# DualExpVCA.net
KiCad netlist of a schematic drawn in EAGLE
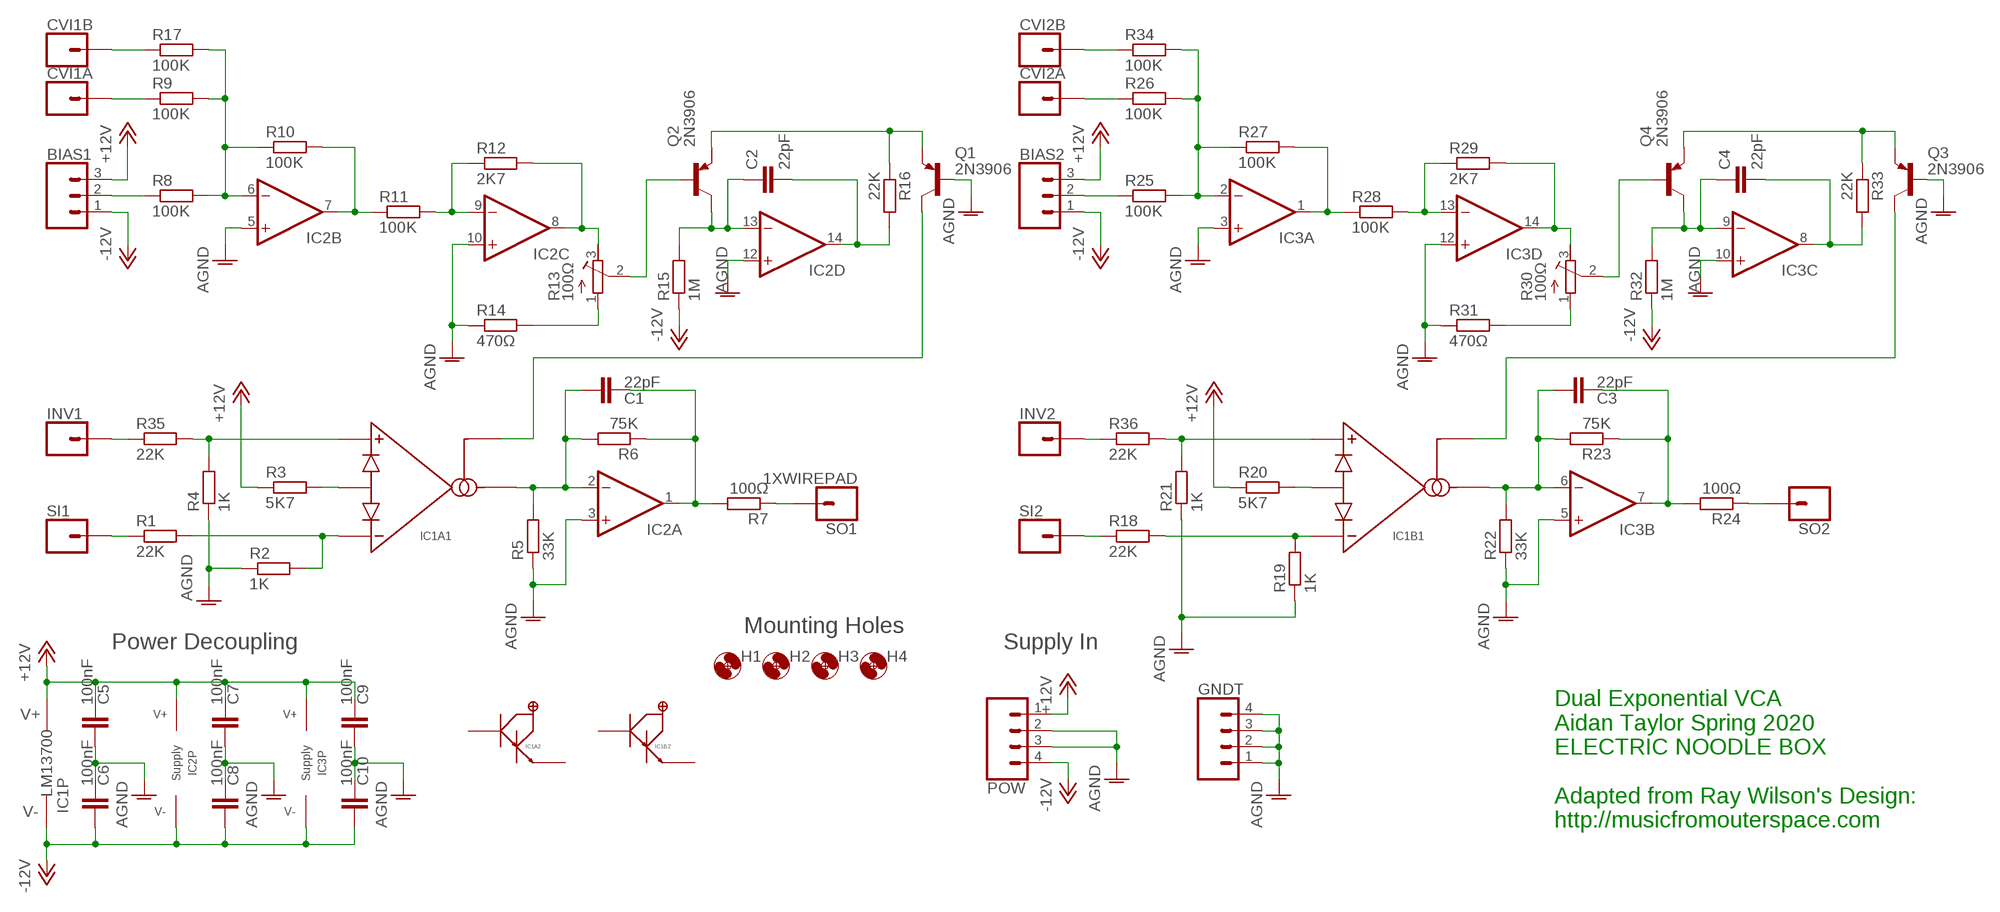
[diagram p0: schematic, sheet 1]

(export (version "E")
  (design (tool "Eeschema 10.0.6"))
  (components
    (comp (ref "BIAS1")
      (value "3XWIREPAD")
      (footprint "eagle-import:1X03")
      (libsource (lib "eagle-import") (part "3XWIREPAD"))
    )
    (comp (ref "BIAS2")
      (value "3XWIREPAD")
      (footprint "eagle-import:1X03")
      (libsource (lib "eagle-import") (part "3XWIREPAD"))
    )
    (comp (ref "C1")
      (value "22pF")
      (footprint "eagle-import:C050-025X075")
      (libsource (lib "eagle-import") (part "C-EU050-025X075"))
    )
    (comp (ref "C2")
      (value "22pF")
      (footprint "eagle-import:C050-025X075")
      (libsource (lib "eagle-import") (part "C-EU050-025X075"))
    )
    (comp (ref "C3")
      (value "22pF")
      (footprint "eagle-import:C050-025X075")
      (libsource (lib "eagle-import") (part "C-EU050-025X075"))
    )
    (comp (ref "C4")
      (value "22pF")
      (footprint "eagle-import:C050-025X075")
      (libsource (lib "eagle-import") (part "C-EU050-025X075"))
    )
    (comp (ref "C5")
      (value "100nF")
      (footprint "eagle-import:C050-025X075")
      (libsource (lib "eagle-import") (part "C-EU050-025X075"))
    )
    (comp (ref "C6")
      (value "100nF")
      (footprint "eagle-import:C050-025X075")
      (libsource (lib "eagle-import") (part "C-EU050-025X075"))
    )
    (comp (ref "C7")
      (value "100nF")
      (footprint "eagle-import:C050-025X075")
      (libsource (lib "eagle-import") (part "C-EU050-025X075"))
    )
    (comp (ref "C8")
      (value "100nF")
      (footprint "eagle-import:C050-025X075")
      (libsource (lib "eagle-import") (part "C-EU050-025X075"))
    )
    (comp (ref "C9")
      (value "100nF")
      (footprint "eagle-import:C050-025X075")
      (libsource (lib "eagle-import") (part "C-EU050-025X075"))
    )
    (comp (ref "C10")
      (value "100nF")
      (footprint "eagle-import:C050-025X075")
      (libsource (lib "eagle-import") (part "C-EU050-025X075"))
    )
    (comp (ref "CVI1A")
      (value "1XWIREPAD")
      (footprint "eagle-import:1X01")
      (libsource (lib "eagle-import") (part "1XWIREPAD"))
    )
    (comp (ref "CVI1B")
      (value "1XWIREPAD")
      (footprint "eagle-import:1X01")
      (libsource (lib "eagle-import") (part "1XWIREPAD"))
    )
    (comp (ref "CVI2A")
      (value "1XWIREPAD")
      (footprint "eagle-import:1X01")
      (libsource (lib "eagle-import") (part "1XWIREPAD"))
    )
    (comp (ref "CVI2B")
      (value "1XWIREPAD")
      (footprint "eagle-import:1X01")
      (libsource (lib "eagle-import") (part "1XWIREPAD"))
    )
    (comp (ref "GNDT")
      (value "4XWIREPAD")
      (footprint "eagle-import:1X04")
      (libsource (lib "eagle-import") (part "4XWIREPAD"))
    )
    (comp (ref "H1")
      (value "MOUNT-HOLE3.2")
      (footprint "eagle-import:3,2")
      (libsource (lib "eagle-import") (part "MOUNT-HOLE3.2"))
    )
    (comp (ref "H2")
      (value "MOUNT-HOLE3.2")
      (footprint "eagle-import:3,2")
      (libsource (lib "eagle-import") (part "MOUNT-HOLE3.2"))
    )
    (comp (ref "H3")
      (value "MOUNT-HOLE3.2")
      (footprint "eagle-import:3,2")
      (libsource (lib "eagle-import") (part "MOUNT-HOLE3.2"))
    )
    (comp (ref "H4")
      (value "MOUNT-HOLE3.2")
      (footprint "eagle-import:3,2")
      (libsource (lib "eagle-import") (part "MOUNT-HOLE3.2"))
    )
    (comp (ref "IC1")
      (value "LM13700_DIP")
      (footprint "eagle-import:DIL16")
      (libsource (lib "eagle-import") (part "LM13700_DIP"))
    )
    (comp (ref "IC2")
      (value "TL0X4_DIP")
      (footprint "eagle-import:DIL14")
      (libsource (lib "eagle-import") (part "TL0X4_DIP"))
    )
    (comp (ref "IC3")
      (value "TL0X4_DIP")
      (footprint "eagle-import:DIL14")
      (libsource (lib "eagle-import") (part "TL0X4_DIP"))
    )
    (comp (ref "INV1")
      (value "1XWIREPAD")
      (footprint "eagle-import:1X01")
      (libsource (lib "eagle-import") (part "1XWIREPAD"))
    )
    (comp (ref "INV2")
      (value "1XWIREPAD")
      (footprint "eagle-import:1X01")
      (libsource (lib "eagle-import") (part "1XWIREPAD"))
    )
    (comp (ref "POW")
      (value "4XMOLEX")
      (footprint "eagle-import:MOLEX-1X4")
      (libsource (lib "eagle-import") (part "4XMOLEX"))
    )
    (comp (ref "Q1")
      (value "2N3906")
      (footprint "eagle-import:TO92")
      (libsource (lib "eagle-import") (part "2N3906"))
    )
    (comp (ref "Q2")
      (value "2N3906")
      (footprint "eagle-import:TO92")
      (libsource (lib "eagle-import") (part "2N3906"))
    )
    (comp (ref "Q3")
      (value "2N3906")
      (footprint "eagle-import:TO92")
      (libsource (lib "eagle-import") (part "2N3906"))
    )
    (comp (ref "Q4")
      (value "2N3906")
      (footprint "eagle-import:TO92")
      (libsource (lib "eagle-import") (part "2N3906"))
    )
    (comp (ref "R1")
      (value "22K")
      (footprint "eagle-import:0207_10")
      (libsource (lib "eagle-import") (part "R-EU_0207/10"))
    )
    (comp (ref "R2")
      (value "1K")
      (footprint "eagle-import:0207_10")
      (libsource (lib "eagle-import") (part "R-EU_0207/10"))
    )
    (comp (ref "R3")
      (value "5K7")
      (footprint "eagle-import:0207_10")
      (libsource (lib "eagle-import") (part "R-EU_0207/10"))
    )
    (comp (ref "R4")
      (value "1K")
      (footprint "eagle-import:0207_10")
      (libsource (lib "eagle-import") (part "R-EU_0207/10"))
    )
    (comp (ref "R5")
      (value "33K")
      (footprint "eagle-import:0207_10")
      (libsource (lib "eagle-import") (part "R-EU_0207/10"))
    )
    (comp (ref "R6")
      (value "75K")
      (footprint "eagle-import:0207_10")
      (libsource (lib "eagle-import") (part "R-EU_0207/10"))
    )
    (comp (ref "R7")
      (value "100Ω")
      (footprint "eagle-import:0207_10")
      (libsource (lib "eagle-import") (part "R-EU_0207/10"))
    )
    (comp (ref "R8")
      (value "100K")
      (footprint "eagle-import:0207_10")
      (libsource (lib "eagle-import") (part "R-EU_0207/10"))
    )
    (comp (ref "R9")
      (value "100K")
      (footprint "eagle-import:0207_10")
      (libsource (lib "eagle-import") (part "R-EU_0207/10"))
    )
    (comp (ref "R10")
      (value "100K")
      (footprint "eagle-import:0207_10")
      (libsource (lib "eagle-import") (part "R-EU_0207/10"))
    )
    (comp (ref "R11")
      (value "100K")
      (footprint "eagle-import:0207_10")
      (libsource (lib "eagle-import") (part "R-EU_0207/10"))
    )
    (comp (ref "R12")
      (value "2K7")
      (footprint "eagle-import:0207_10")
      (libsource (lib "eagle-import") (part "R-EU_0207/10"))
    )
    (comp (ref "R13")
      (value "100Ω")
      (footprint "eagle-import:RTRIM3296W")
      (libsource (lib "eagle-import") (part "R-TRIMM3296W"))
    )
    (comp (ref "R14")
      (value "470Ω")
      (footprint "eagle-import:0207_10")
      (libsource (lib "eagle-import") (part "R-EU_0207/10"))
    )
    (comp (ref "R15")
      (value "1M")
      (footprint "eagle-import:0207_10")
      (libsource (lib "eagle-import") (part "R-EU_0207/10"))
    )
    (comp (ref "R16")
      (value "22K")
      (footprint "eagle-import:0207_10")
      (libsource (lib "eagle-import") (part "R-EU_0207/10"))
    )
    (comp (ref "R17")
      (value "100K")
      (footprint "eagle-import:0207_10")
      (libsource (lib "eagle-import") (part "R-EU_0207/10"))
    )
    (comp (ref "R18")
      (value "22K")
      (footprint "eagle-import:0207_10")
      (libsource (lib "eagle-import") (part "R-EU_0207/10"))
    )
    (comp (ref "R19")
      (value "1K")
      (footprint "eagle-import:0207_10")
      (libsource (lib "eagle-import") (part "R-EU_0207/10"))
    )
    (comp (ref "R20")
      (value "5K7")
      (footprint "eagle-import:0207_10")
      (libsource (lib "eagle-import") (part "R-EU_0207/10"))
    )
    (comp (ref "R21")
      (value "1K")
      (footprint "eagle-import:0207_10")
      (libsource (lib "eagle-import") (part "R-EU_0207/10"))
    )
    (comp (ref "R22")
      (value "33K")
      (footprint "eagle-import:0207_10")
      (libsource (lib "eagle-import") (part "R-EU_0207/10"))
    )
    (comp (ref "R23")
      (value "75K")
      (footprint "eagle-import:0207_10")
      (libsource (lib "eagle-import") (part "R-EU_0207/10"))
    )
    (comp (ref "R24")
      (value "100Ω")
      (footprint "eagle-import:0207_10")
      (libsource (lib "eagle-import") (part "R-EU_0207/10"))
    )
    (comp (ref "R25")
      (value "100K")
      (footprint "eagle-import:0207_10")
      (libsource (lib "eagle-import") (part "R-EU_0207/10"))
    )
    (comp (ref "R26")
      (value "100K")
      (footprint "eagle-import:0207_10")
      (libsource (lib "eagle-import") (part "R-EU_0207/10"))
    )
    (comp (ref "R27")
      (value "100K")
      (footprint "eagle-import:0207_10")
      (libsource (lib "eagle-import") (part "R-EU_0207/10"))
    )
    (comp (ref "R28")
      (value "100K")
      (footprint "eagle-import:0207_10")
      (libsource (lib "eagle-import") (part "R-EU_0207/10"))
    )
    (comp (ref "R29")
      (value "2K7")
      (footprint "eagle-import:0207_10")
      (libsource (lib "eagle-import") (part "R-EU_0207/10"))
    )
    (comp (ref "R30")
      (value "100Ω")
      (footprint "eagle-import:RTRIM3296W")
      (libsource (lib "eagle-import") (part "R-TRIMM3296W"))
    )
    (comp (ref "R31")
      (value "470Ω")
      (footprint "eagle-import:0207_10")
      (libsource (lib "eagle-import") (part "R-EU_0207/10"))
    )
    (comp (ref "R32")
      (value "1M")
      (footprint "eagle-import:0207_10")
      (libsource (lib "eagle-import") (part "R-EU_0207/10"))
    )
    (comp (ref "R33")
      (value "22K")
      (footprint "eagle-import:0207_10")
      (libsource (lib "eagle-import") (part "R-EU_0207/10"))
    )
    (comp (ref "R34")
      (value "100K")
      (footprint "eagle-import:0207_10")
      (libsource (lib "eagle-import") (part "R-EU_0207/10"))
    )
    (comp (ref "R35")
      (value "22K")
      (footprint "eagle-import:0207_10")
      (libsource (lib "eagle-import") (part "R-EU_0207/10"))
    )
    (comp (ref "R36")
      (value "22K")
      (footprint "eagle-import:0207_10")
      (libsource (lib "eagle-import") (part "R-EU_0207/10"))
    )
    (comp (ref "SI1")
      (value "1XWIREPAD")
      (footprint "eagle-import:1X01")
      (libsource (lib "eagle-import") (part "1XWIREPAD"))
    )
    (comp (ref "SI2")
      (value "1XWIREPAD")
      (footprint "eagle-import:1X01")
      (libsource (lib "eagle-import") (part "1XWIREPAD"))
    )
    (comp (ref "SO1")
      (value "1XWIREPAD")
      (footprint "eagle-import:1X01")
      (libsource (lib "eagle-import") (part "1XWIREPAD"))
    )
    (comp (ref "SO2")
      (value "1XWIREPAD")
      (footprint "eagle-import:1X01")
      (libsource (lib "eagle-import") (part "1XWIREPAD"))
    )
  )
  (nets
    (net (code "1") (name "+12V") (class "Default")
      (node (ref "BIAS1") (pin "3") (pinfunction "3_3") (pintype "passive"))
      (node (ref "BIAS2") (pin "3") (pinfunction "3_3") (pintype "passive"))
      (node (ref "C5") (pin "2") (pinfunction "2_2") (pintype "passive"))
      (node (ref "C7") (pin "2") (pinfunction "2_2") (pintype "passive"))
      (node (ref "C9") (pin "2") (pinfunction "2_2") (pintype "passive"))
      (node (ref "IC1") (pin "11") (pinfunction "V+_11") (pintype "power_in"))
      (node (ref "IC2") (pin "4") (pinfunction "V+_4") (pintype "bidirectional"))
      (node (ref "IC3") (pin "4") (pinfunction "V+_4") (pintype "bidirectional"))
      (node (ref "POW") (pin "1") (pinfunction "1_1") (pintype "passive"))
      (node (ref "R20") (pin "1") (pinfunction "1_1") (pintype "passive"))
      (node (ref "R3") (pin "1") (pinfunction "1_1") (pintype "passive"))
    )
    (net (code "2") (name "-12V") (class "Default")
      (node (ref "BIAS1") (pin "1") (pinfunction "1_1") (pintype "passive"))
      (node (ref "BIAS2") (pin "1") (pinfunction "1_1") (pintype "passive"))
      (node (ref "C10") (pin "1") (pinfunction "1_1") (pintype "passive"))
      (node (ref "C6") (pin "1") (pinfunction "1_1") (pintype "passive"))
      (node (ref "C8") (pin "1") (pinfunction "1_1") (pintype "passive"))
      (node (ref "IC1") (pin "6") (pinfunction "V-_6") (pintype "power_in"))
      (node (ref "IC2") (pin "11") (pinfunction "V-_11") (pintype "bidirectional"))
      (node (ref "IC3") (pin "11") (pinfunction "V-_11") (pintype "bidirectional"))
      (node (ref "POW") (pin "4") (pinfunction "4_4") (pintype "passive"))
      (node (ref "R15") (pin "1") (pinfunction "1_1") (pintype "passive"))
      (node (ref "R32") (pin "1") (pinfunction "1_1") (pintype "passive"))
    )
    (net (code "3") (name "AGND") (class "Default")
      (node (ref "C10") (pin "2") (pinfunction "2_2") (pintype "passive"))
      (node (ref "C5") (pin "1") (pinfunction "1_1") (pintype "passive"))
      (node (ref "C6") (pin "2") (pinfunction "2_2") (pintype "passive"))
      (node (ref "C7") (pin "1") (pinfunction "1_1") (pintype "passive"))
      (node (ref "C8") (pin "2") (pinfunction "2_2") (pintype "passive"))
      (node (ref "C9") (pin "1") (pinfunction "1_1") (pintype "passive"))
      (node (ref "GNDT") (pin "1") (pinfunction "1_1") (pintype "passive"))
      (node (ref "GNDT") (pin "2") (pinfunction "2_2") (pintype "passive"))
      (node (ref "GNDT") (pin "3") (pinfunction "3_3") (pintype "passive"))
      (node (ref "GNDT") (pin "4") (pinfunction "4_4") (pintype "passive"))
      (node (ref "IC2") (pin "10") (pinfunction "+IN_10") (pintype "input"))
      (node (ref "IC2") (pin "12") (pinfunction "+IN_12") (pintype "input"))
      (node (ref "IC2") (pin "3") (pinfunction "+IN_3") (pintype "input"))
      (node (ref "IC2") (pin "5") (pinfunction "+IN_5") (pintype "input"))
      (node (ref "IC3") (pin "10") (pinfunction "+IN_10") (pintype "input"))
      (node (ref "IC3") (pin "12") (pinfunction "+IN_12") (pintype "input"))
      (node (ref "IC3") (pin "3") (pinfunction "+IN_3") (pintype "input"))
      (node (ref "IC3") (pin "5") (pinfunction "+IN_5") (pintype "input"))
      (node (ref "POW") (pin "2") (pinfunction "2_2") (pintype "passive"))
      (node (ref "POW") (pin "3") (pinfunction "3_3") (pintype "passive"))
      (node (ref "Q1") (pin "2") (pinfunction "B_2") (pintype "passive"))
      (node (ref "Q3") (pin "2") (pinfunction "B_2") (pintype "passive"))
      (node (ref "R14") (pin "1") (pinfunction "1_1") (pintype "passive"))
      (node (ref "R19") (pin "1") (pinfunction "1_1") (pintype "passive"))
      (node (ref "R2") (pin "1") (pinfunction "1_1") (pintype "passive"))
      (node (ref "R21") (pin "1") (pinfunction "1_1") (pintype "passive"))
      (node (ref "R22") (pin "1") (pinfunction "1_1") (pintype "passive"))
      (node (ref "R31") (pin "1") (pinfunction "1_1") (pintype "passive"))
      (node (ref "R4") (pin "1") (pinfunction "1_1") (pintype "passive"))
      (node (ref "R5") (pin "1") (pinfunction "1_1") (pintype "passive"))
    )
    (net (code "4") (name "Net-(BIAS1-Pad2)") (class "Default")
      (node (ref "BIAS1") (pin "2") (pinfunction "2_2") (pintype "passive"))
      (node (ref "R8") (pin "1") (pinfunction "1_1") (pintype "passive"))
    )
    (net (code "5") (name "Net-(BIAS2-Pad2)") (class "Default")
      (node (ref "BIAS2") (pin "2") (pinfunction "2_2") (pintype "passive"))
      (node (ref "R25") (pin "1") (pinfunction "1_1") (pintype "passive"))
    )
    (net (code "6") (name "Net-(CVI1A-Pad1)") (class "Default")
      (node (ref "CVI1A") (pin "1") (pinfunction "1_1") (pintype "passive"))
      (node (ref "R9") (pin "1") (pinfunction "1_1") (pintype "passive"))
    )
    (net (code "7") (name "Net-(CVI1B-Pad1)") (class "Default")
      (node (ref "CVI1B") (pin "1") (pinfunction "1_1") (pintype "passive"))
      (node (ref "R17") (pin "1") (pinfunction "1_1") (pintype "passive"))
    )
    (net (code "8") (name "Net-(CVI2A-Pad1)") (class "Default")
      (node (ref "CVI2A") (pin "1") (pinfunction "1_1") (pintype "passive"))
      (node (ref "R26") (pin "1") (pinfunction "1_1") (pintype "passive"))
    )
    (net (code "9") (name "Net-(CVI2B-Pad1)") (class "Default")
      (node (ref "CVI2B") (pin "1") (pinfunction "1_1") (pintype "passive"))
      (node (ref "R34") (pin "1") (pinfunction "1_1") (pintype "passive"))
    )
    (net (code "10") (name "Net-(IC1A-AMP+)") (class "Default")
      (node (ref "IC1") (pin "3") (pinfunction "AMP+_3") (pintype "input"))
      (node (ref "R35") (pin "2") (pinfunction "2_2") (pintype "passive"))
      (node (ref "R4") (pin "2") (pinfunction "2_2") (pintype "passive"))
    )
    (net (code "11") (name "Net-(IC1A-AMP-)") (class "Default")
      (node (ref "IC1") (pin "4") (pinfunction "AMP-_4") (pintype "input"))
      (node (ref "R1") (pin "2") (pinfunction "2_2") (pintype "passive"))
      (node (ref "R2") (pin "2") (pinfunction "2_2") (pintype "passive"))
    )
    (net (code "12") (name "Net-(IC1A-AMPBIAS)") (class "Default")
      (node (ref "IC1") (pin "1") (pinfunction "AMPBIAS_1") (pintype "input"))
      (node (ref "Q1") (pin "1") (pinfunction "C_1") (pintype "passive"))
    )
    (net (code "13") (name "Net-(IC1A-AMPOUT)") (class "Default")
      (node (ref "C1") (pin "1") (pinfunction "1_1") (pintype "passive"))
      (node (ref "IC1") (pin "5") (pinfunction "AMPOUT_5") (pintype "output"))
      (node (ref "IC2") (pin "2") (pinfunction "-IN_2") (pintype "input"))
      (node (ref "R5") (pin "2") (pinfunction "2_2") (pintype "passive"))
      (node (ref "R6") (pin "2") (pinfunction "2_2") (pintype "passive"))
    )
    (net (code "14") (name "Net-(IC1A-DIODES)") (class "Default")
      (node (ref "IC1") (pin "2") (pinfunction "DIODES_2") (pintype "input"))
      (node (ref "R3") (pin "2") (pinfunction "2_2") (pintype "passive"))
    )
    (net (code "15") (name "Net-(IC1C-AMP+)") (class "Default")
      (node (ref "IC1") (pin "14") (pinfunction "AMP+_14") (pintype "input"))
      (node (ref "R21") (pin "2") (pinfunction "2_2") (pintype "passive"))
      (node (ref "R36") (pin "2") (pinfunction "2_2") (pintype "passive"))
    )
    (net (code "16") (name "Net-(IC1C-AMP-)") (class "Default")
      (node (ref "IC1") (pin "13") (pinfunction "AMP-_13") (pintype "input"))
      (node (ref "R18") (pin "2") (pinfunction "2_2") (pintype "passive"))
      (node (ref "R19") (pin "2") (pinfunction "2_2") (pintype "passive"))
    )
    (net (code "17") (name "Net-(IC1C-AMPBIAS)") (class "Default")
      (node (ref "IC1") (pin "16") (pinfunction "AMPBIAS_16") (pintype "input"))
      (node (ref "Q3") (pin "1") (pinfunction "C_1") (pintype "passive"))
    )
    (net (code "18") (name "Net-(IC1C-AMPOUT)") (class "Default")
      (node (ref "C3") (pin "1") (pinfunction "1_1") (pintype "passive"))
      (node (ref "IC1") (pin "12") (pinfunction "AMPOUT_12") (pintype "output"))
      (node (ref "IC3") (pin "6") (pinfunction "-IN_6") (pintype "input"))
      (node (ref "R22") (pin "2") (pinfunction "2_2") (pintype "passive"))
      (node (ref "R23") (pin "2") (pinfunction "2_2") (pintype "passive"))
    )
    (net (code "19") (name "Net-(IC1C-DIODES)") (class "Default")
      (node (ref "IC1") (pin "15") (pinfunction "DIODES_15") (pintype "input"))
      (node (ref "R20") (pin "2") (pinfunction "2_2") (pintype "passive"))
    )
    (net (code "20") (name "Net-(IC2A-OUT)") (class "Default")
      (node (ref "C1") (pin "2") (pinfunction "2_2") (pintype "passive"))
      (node (ref "IC2") (pin "1") (pinfunction "OUT_1") (pintype "output"))
      (node (ref "R6") (pin "1") (pinfunction "1_1") (pintype "passive"))
      (node (ref "R7") (pin "2") (pinfunction "2_2") (pintype "passive"))
    )
    (net (code "21") (name "Net-(IC2B--IN)") (class "Default")
      (node (ref "IC2") (pin "6") (pinfunction "-IN_6") (pintype "input"))
      (node (ref "R10") (pin "1") (pinfunction "1_1") (pintype "passive"))
      (node (ref "R17") (pin "2") (pinfunction "2_2") (pintype "passive"))
      (node (ref "R8") (pin "2") (pinfunction "2_2") (pintype "passive"))
      (node (ref "R9") (pin "2") (pinfunction "2_2") (pintype "passive"))
    )
    (net (code "22") (name "Net-(IC2B-OUT)") (class "Default")
      (node (ref "IC2") (pin "7") (pinfunction "OUT_7") (pintype "output"))
      (node (ref "R10") (pin "2") (pinfunction "2_2") (pintype "passive"))
      (node (ref "R11") (pin "1") (pinfunction "1_1") (pintype "passive"))
    )
    (net (code "23") (name "Net-(IC2C--IN)") (class "Default")
      (node (ref "IC2") (pin "9") (pinfunction "-IN_9") (pintype "input"))
      (node (ref "R11") (pin "2") (pinfunction "2_2") (pintype "passive"))
      (node (ref "R12") (pin "1") (pinfunction "1_1") (pintype "passive"))
    )
    (net (code "24") (name "Net-(IC2C-OUT)") (class "Default")
      (node (ref "IC2") (pin "8") (pinfunction "OUT_8") (pintype "output"))
      (node (ref "R12") (pin "2") (pinfunction "2_2") (pintype "passive"))
      (node (ref "R13") (pin "3") (pinfunction "E_3") (pintype "passive"))
    )
    (net (code "25") (name "Net-(IC2D--IN)") (class "Default")
      (node (ref "C2") (pin "1") (pinfunction "1_1") (pintype "passive"))
      (node (ref "IC2") (pin "13") (pinfunction "-IN_13") (pintype "input"))
      (node (ref "Q2") (pin "1") (pinfunction "C_1") (pintype "passive"))
      (node (ref "R15") (pin "2") (pinfunction "2_2") (pintype "passive"))
    )
    (net (code "26") (name "Net-(IC2D-OUT)") (class "Default")
      (node (ref "C2") (pin "2") (pinfunction "2_2") (pintype "passive"))
      (node (ref "IC2") (pin "14") (pinfunction "OUT_14") (pintype "output"))
      (node (ref "R16") (pin "2") (pinfunction "2_2") (pintype "passive"))
    )
    (net (code "27") (name "Net-(IC3A--IN)") (class "Default")
      (node (ref "IC3") (pin "2") (pinfunction "-IN_2") (pintype "input"))
      (node (ref "R25") (pin "2") (pinfunction "2_2") (pintype "passive"))
      (node (ref "R26") (pin "2") (pinfunction "2_2") (pintype "passive"))
      (node (ref "R27") (pin "1") (pinfunction "1_1") (pintype "passive"))
      (node (ref "R34") (pin "2") (pinfunction "2_2") (pintype "passive"))
    )
    (net (code "28") (name "Net-(IC3A-OUT)") (class "Default")
      (node (ref "IC3") (pin "1") (pinfunction "OUT_1") (pintype "output"))
      (node (ref "R27") (pin "2") (pinfunction "2_2") (pintype "passive"))
      (node (ref "R28") (pin "1") (pinfunction "1_1") (pintype "passive"))
    )
    (net (code "29") (name "Net-(IC3B-OUT)") (class "Default")
      (node (ref "C3") (pin "2") (pinfunction "2_2") (pintype "passive"))
      (node (ref "IC3") (pin "7") (pinfunction "OUT_7") (pintype "output"))
      (node (ref "R23") (pin "1") (pinfunction "1_1") (pintype "passive"))
      (node (ref "R24") (pin "2") (pinfunction "2_2") (pintype "passive"))
    )
    (net (code "30") (name "Net-(IC3C--IN)") (class "Default")
      (node (ref "C4") (pin "1") (pinfunction "1_1") (pintype "passive"))
      (node (ref "IC3") (pin "9") (pinfunction "-IN_9") (pintype "input"))
      (node (ref "Q4") (pin "1") (pinfunction "C_1") (pintype "passive"))
      (node (ref "R32") (pin "2") (pinfunction "2_2") (pintype "passive"))
    )
    (net (code "31") (name "Net-(IC3C-OUT)") (class "Default")
      (node (ref "C4") (pin "2") (pinfunction "2_2") (pintype "passive"))
      (node (ref "IC3") (pin "8") (pinfunction "OUT_8") (pintype "output"))
      (node (ref "R33") (pin "2") (pinfunction "2_2") (pintype "passive"))
    )
    (net (code "32") (name "Net-(IC3D--IN)") (class "Default")
      (node (ref "IC3") (pin "13") (pinfunction "-IN_13") (pintype "input"))
      (node (ref "R28") (pin "2") (pinfunction "2_2") (pintype "passive"))
      (node (ref "R29") (pin "1") (pinfunction "1_1") (pintype "passive"))
    )
    (net (code "33") (name "Net-(IC3D-OUT)") (class "Default")
      (node (ref "IC3") (pin "14") (pinfunction "OUT_14") (pintype "output"))
      (node (ref "R29") (pin "2") (pinfunction "2_2") (pintype "passive"))
      (node (ref "R30") (pin "3") (pinfunction "E_3") (pintype "passive"))
    )
    (net (code "34") (name "Net-(INV1-Pad1)") (class "Default")
      (node (ref "INV1") (pin "1") (pinfunction "1_1") (pintype "passive"))
      (node (ref "R35") (pin "1") (pinfunction "1_1") (pintype "passive"))
    )
    (net (code "35") (name "Net-(INV2-Pad1)") (class "Default")
      (node (ref "INV2") (pin "1") (pinfunction "1_1") (pintype "passive"))
      (node (ref "R36") (pin "1") (pinfunction "1_1") (pintype "passive"))
    )
    (net (code "36") (name "Net-(Q1-E)") (class "Default")
      (node (ref "Q1") (pin "3") (pinfunction "E_3") (pintype "passive"))
      (node (ref "Q2") (pin "3") (pinfunction "E_3") (pintype "passive"))
      (node (ref "R16") (pin "1") (pinfunction "1_1") (pintype "passive"))
    )
    (net (code "37") (name "Net-(Q2-B)") (class "Default")
      (node (ref "Q2") (pin "2") (pinfunction "B_2") (pintype "passive"))
      (node (ref "R13") (pin "2") (pinfunction "S_2") (pintype "passive"))
    )
    (net (code "38") (name "Net-(Q3-E)") (class "Default")
      (node (ref "Q3") (pin "3") (pinfunction "E_3") (pintype "passive"))
      (node (ref "Q4") (pin "3") (pinfunction "E_3") (pintype "passive"))
      (node (ref "R33") (pin "1") (pinfunction "1_1") (pintype "passive"))
    )
    (net (code "39") (name "Net-(Q4-B)") (class "Default")
      (node (ref "Q4") (pin "2") (pinfunction "B_2") (pintype "passive"))
      (node (ref "R30") (pin "2") (pinfunction "S_2") (pintype "passive"))
    )
    (net (code "40") (name "Net-(R1-Pad1)") (class "Default")
      (node (ref "R1") (pin "1") (pinfunction "1_1") (pintype "passive"))
      (node (ref "SI1") (pin "1") (pinfunction "1_1") (pintype "passive"))
    )
    (net (code "41") (name "Net-(R7-Pad1)") (class "Default")
      (node (ref "R7") (pin "1") (pinfunction "1_1") (pintype "passive"))
      (node (ref "SO1") (pin "1") (pinfunction "1_1") (pintype "passive"))
    )
    (net (code "42") (name "Net-(R13-A)") (class "Default")
      (node (ref "R13") (pin "1") (pinfunction "A_1") (pintype "passive"))
      (node (ref "R14") (pin "2") (pinfunction "2_2") (pintype "passive"))
    )
    (net (code "43") (name "Net-(R18-Pad1)") (class "Default")
      (node (ref "R18") (pin "1") (pinfunction "1_1") (pintype "passive"))
      (node (ref "SI2") (pin "1") (pinfunction "1_1") (pintype "passive"))
    )
    (net (code "44") (name "Net-(R24-Pad1)") (class "Default")
      (node (ref "R24") (pin "1") (pinfunction "1_1") (pintype "passive"))
      (node (ref "SO2") (pin "1") (pinfunction "1_1") (pintype "passive"))
    )
    (net (code "45") (name "Net-(R30-A)") (class "Default")
      (node (ref "R30") (pin "1") (pinfunction "A_1") (pintype "passive"))
      (node (ref "R31") (pin "2") (pinfunction "2_2") (pintype "passive"))
    )
    (net (code "46") (name "unconnected-(IC1B-BUFF_IN-Pad7)") (class "Default")
      (node (ref "IC1") (pin "7") (pinfunction "BUFF_IN_7") (pintype "input"))
    )
    (net (code "47") (name "unconnected-(IC1B-BUFF_OUT-Pad8)") (class "Default")
      (node (ref "IC1") (pin "8") (pinfunction "BUFF_OUT_8") (pintype "bidirectional"))
    )
    (net (code "48") (name "unconnected-(IC1D-BUFF_IN-Pad10)") (class "Default")
      (node (ref "IC1") (pin "10") (pinfunction "BUFF_IN_10") (pintype "input"))
    )
    (net (code "49") (name "unconnected-(IC1D-BUFF_OUT-Pad9)") (class "Default")
      (node (ref "IC1") (pin "9") (pinfunction "BUFF_OUT_9") (pintype "bidirectional"))
    )
  )
)
